# RGB.net
KiCad netlist of a schematic drawn in Altium Designer
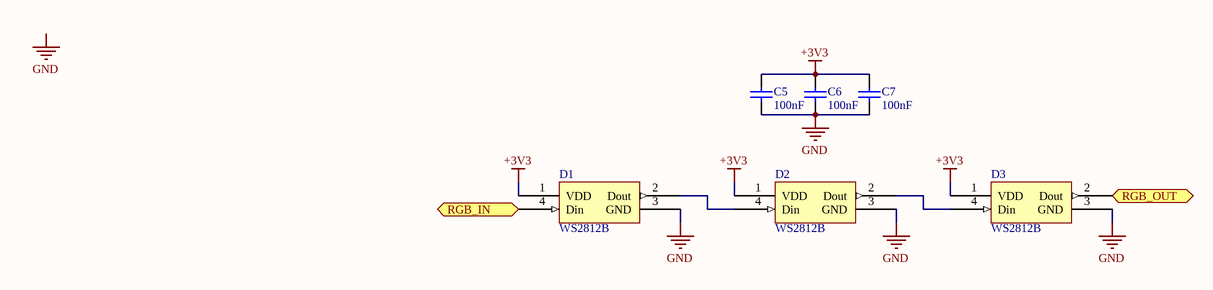
[diagram p0: RGB.SchDoc]

(export (version "E")
  (design (tool "Eeschema 10.0.6"))
  (components
    (comp (ref "C5")
      (value "100nF")
      (footprint "CAP_0805_IPC_MD")
      (description "Capacitor")
      (fields (field (name "MANUFACTURER") "Samsung") (field (name "Comment") "Cap"))
      (libsource (lib "DataLogger") (part "Cap"))
    )
    (comp (ref "C6")
      (value "100nF")
      (footprint "CAP_0805_IPC_MD")
      (description "Capacitor")
      (fields (field (name "MANUFACTURER") "Samsung") (field (name "Comment") "Cap"))
      (libsource (lib "DataLogger") (part "Cap"))
    )
    (comp (ref "C7")
      (value "100nF")
      (footprint "CAP_0805_IPC_MD")
      (description "Capacitor")
      (fields (field (name "MANUFACTURER") "Samsung") (field (name "Comment") "Cap"))
      (libsource (lib "DataLogger") (part "Cap"))
    )
    (comp (ref "D1")
      (value "RGB LED")
      (footprint "WS2812B")
      (description "Programmable RGB LED")
      (fields (field (name "MANUFACTURER") "Worldsemi") (field (name "MANUFACTURER PART NUMBER") "WS2812B"))
      (libsource (lib "Dashboard") (part "RGB LED"))
    )
    (comp (ref "D2")
      (value "RGB LED")
      (footprint "WS2812B")
      (description "Programmable RGB LED")
      (fields (field (name "MANUFACTURER") "Worldsemi") (field (name "MANUFACTURER PART NUMBER") "WS2812B"))
      (libsource (lib "Dashboard") (part "RGB LED"))
    )
    (comp (ref "D3")
      (value "RGB LED")
      (footprint "WS2812B")
      (description "Programmable RGB LED")
      (fields (field (name "MANUFACTURER") "Worldsemi") (field (name "MANUFACTURER PART NUMBER") "WS2812B"))
      (libsource (lib "Dashboard") (part "RGB LED"))
    )
  )
  (nets
    (net (code "1") (name "+3V3") (class "Default")
      (node (ref "C5") (pin "2") (pinfunction "2_2") (pintype "passive"))
      (node (ref "C6") (pin "2") (pinfunction "2_2") (pintype "passive"))
      (node (ref "C7") (pin "2") (pinfunction "2_2") (pintype "passive"))
      (node (ref "D1") (pin "1") (pinfunction "VDD_1") (pintype "power_in"))
      (node (ref "D2") (pin "1") (pinfunction "VDD_1") (pintype "power_in"))
      (node (ref "D3") (pin "1") (pinfunction "VDD_1") (pintype "power_in"))
    )
    (net (code "2") (name "/RGB_IN") (class "Default")
      (node (ref "D1") (pin "4") (pinfunction "Din_4") (pintype "input"))
    )
    (net (code "3") (name "/RGB_OUT") (class "Default")
      (node (ref "D3") (pin "2") (pinfunction "Dout_2") (pintype "output"))
    )
    (net (code "4") (name "GND") (class "Default")
      (node (ref "C5") (pin "1") (pinfunction "1_1") (pintype "passive"))
      (node (ref "C6") (pin "1") (pinfunction "1_1") (pintype "passive"))
      (node (ref "C7") (pin "1") (pinfunction "1_1") (pintype "passive"))
      (node (ref "D1") (pin "3") (pinfunction "GND_3") (pintype "power_in"))
      (node (ref "D2") (pin "3") (pinfunction "GND_3") (pintype "power_in"))
      (node (ref "D3") (pin "3") (pinfunction "GND_3") (pintype "power_in"))
    )
    (net (code "5") (name "Net-(D1-Dout)") (class "Default")
      (node (ref "D1") (pin "2") (pinfunction "Dout_2") (pintype "output"))
      (node (ref "D2") (pin "4") (pinfunction "Din_4") (pintype "input"))
    )
    (net (code "6") (name "Net-(D2-Dout)") (class "Default")
      (node (ref "D2") (pin "2") (pinfunction "Dout_2") (pintype "output"))
      (node (ref "D3") (pin "4") (pinfunction "Din_4") (pintype "input"))
    )
  )
)
